# ASD2020.net
KiCad netlist of a schematic drawn in EAGLE
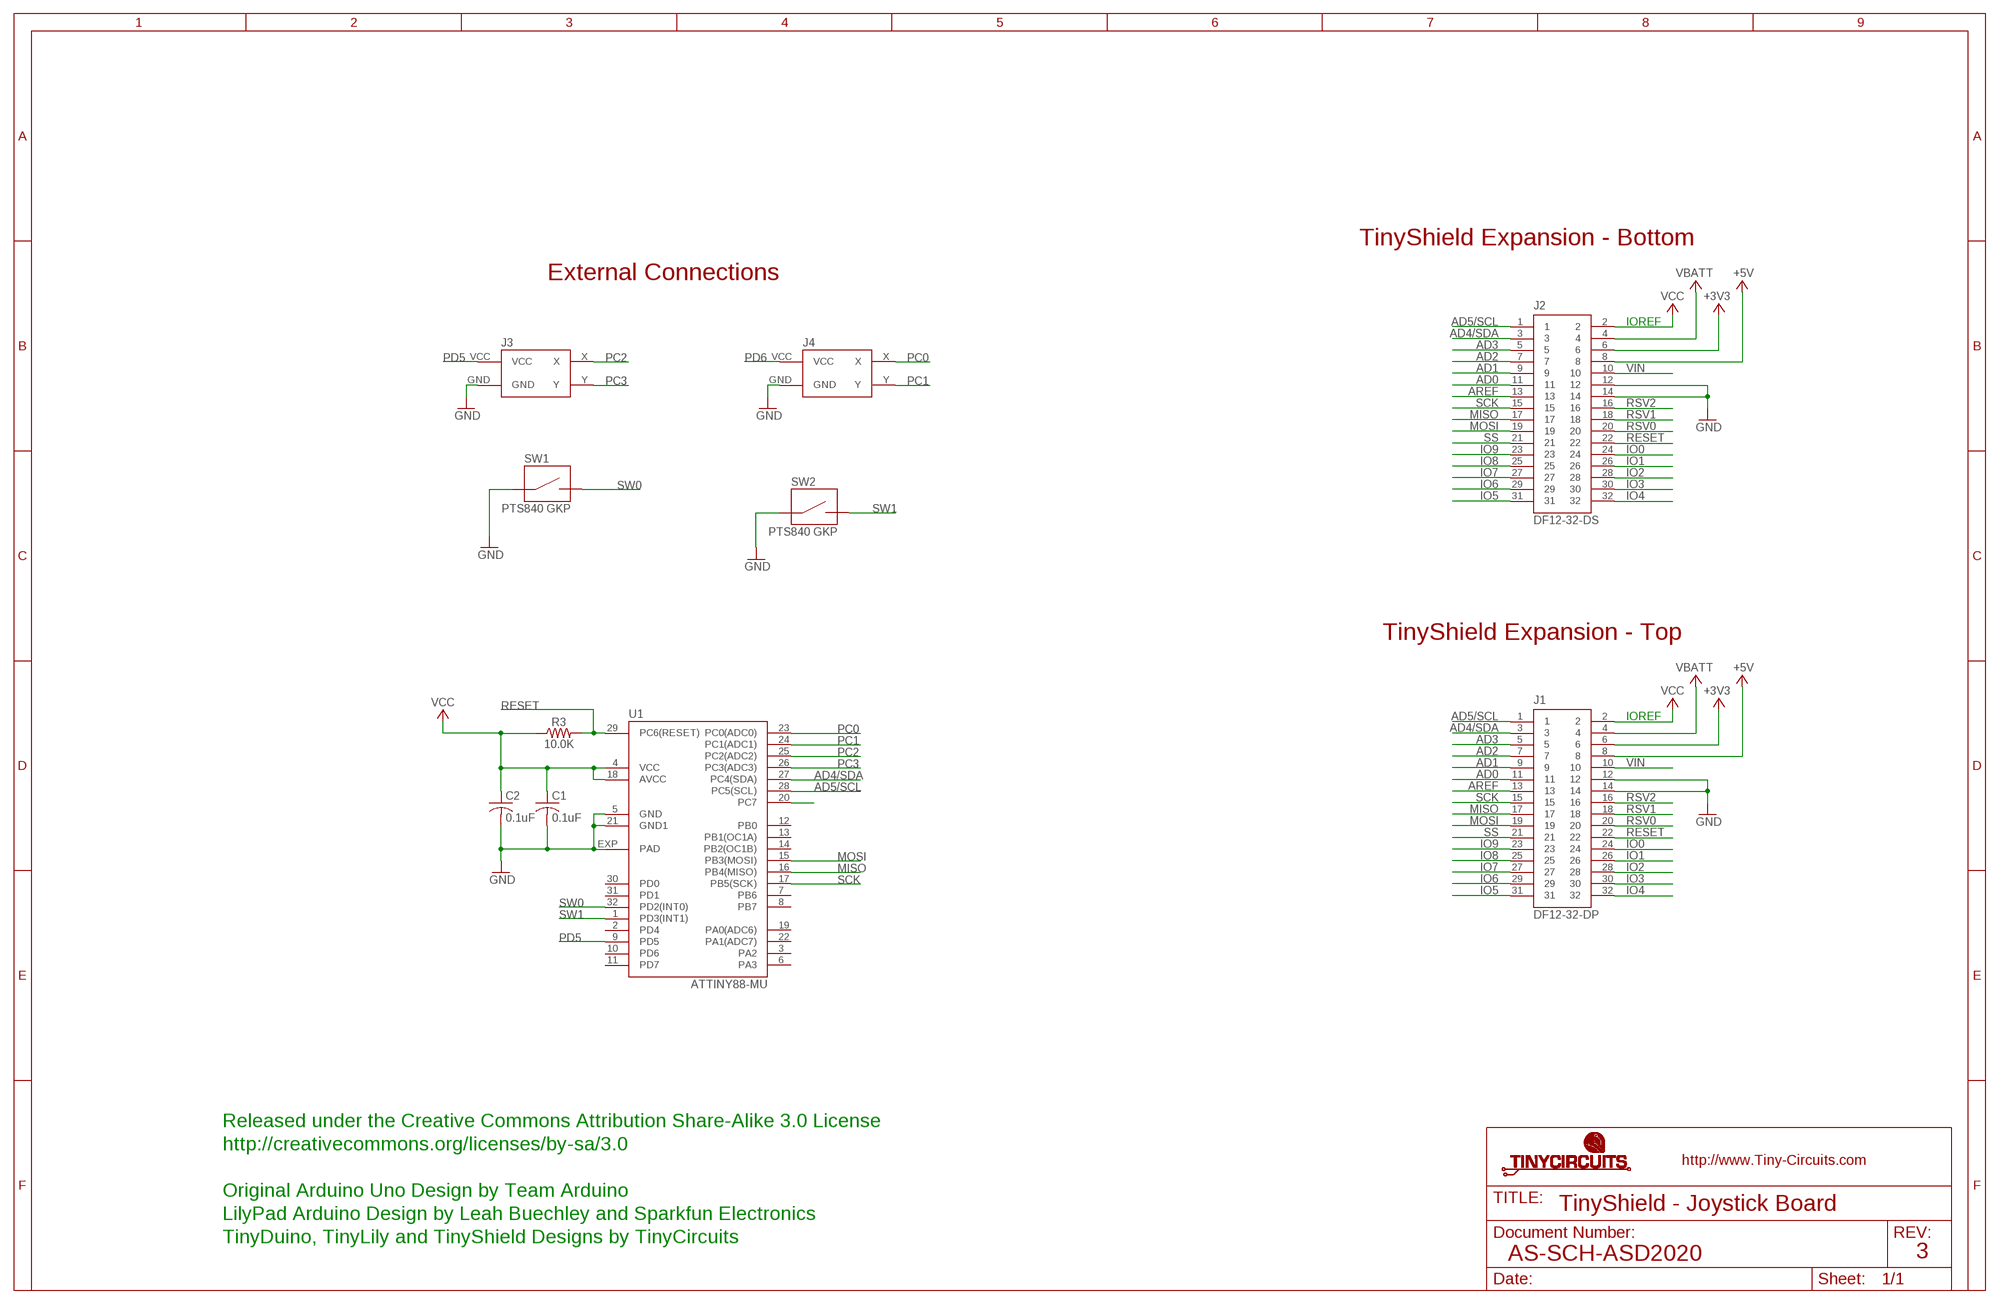
[diagram p0: schematic, sheet 1]

(export (version "E")
  (design (tool "Eeschema 10.0.6"))
  (components
    (comp (ref "C1")
      (value "0.1uF")
      (footprint "eagle-import:C0402")
      (fields (field (name "PARTNO") "AS-ITM-00008"))
      (libsource (lib "eagle-import") (part "AS-ITM-00008"))
    )
    (comp (ref "C2")
      (value "0.1uF")
      (footprint "eagle-import:C0402")
      (fields (field (name "PARTNO") "AS-ITM-00008"))
      (libsource (lib "eagle-import") (part "AS-ITM-00008"))
    )
    (comp (ref "J1")
      (value "DF12-32-DP")
      (footprint "eagle-import:DF12-32-DP")
      (fields (field (name "PARTNO") "AS-ITM-00015") (field (name "PARTNO_1") "AS-ITM-00015"))
      (libsource (lib "eagle-import") (part "AS-ITM-00015"))
    )
    (comp (ref "J2")
      (value "DF12-32-DS")
      (footprint "eagle-import:DF12-32-DS")
      (fields (field (name "PARTNO") "AS-ITM-00012") (field (name "PARTNO_1") "AS-ITM-00012"))
      (libsource (lib "eagle-import") (part "AS-ITM-00012"))
    )
    (comp (ref "J3")
      (value "AS-ITM-00235")
      (footprint "eagle-import:PSPJOYSTICK")
      (libsource (lib "eagle-import") (part "AS-ITM-00235"))
    )
    (comp (ref "J4")
      (value "AS-ITM-00235")
      (footprint "eagle-import:PSPJOYSTICK")
      (libsource (lib "eagle-import") (part "AS-ITM-00235"))
    )
    (comp (ref "R3")
      (value "10.0K")
      (footprint "eagle-import:0402")
      (fields (field (name "PARTNO") "AS-ITM-00032"))
      (libsource (lib "eagle-import") (part "AS-ITM-00032"))
    )
    (comp (ref "SW1")
      (value "PTS840 GKP")
      (footprint "eagle-import:PTS840GKP")
      (fields (field (name "PARTNO") "AS-ITM-00236"))
      (libsource (lib "eagle-import") (part "AS-ITM-00236"))
    )
    (comp (ref "SW2")
      (value "PTS840 GKP")
      (footprint "eagle-import:PTS840GKP")
      (fields (field (name "PARTNO") "AS-ITM-00236"))
      (libsource (lib "eagle-import") (part "AS-ITM-00236"))
    )
    (comp (ref "U1")
      (value "ATTINY88-MU")
      (footprint "eagle-import:ATMEL_QFN32")
      (fields (field (name "PARTNO") "AS-ITM-00214"))
      (libsource (lib "eagle-import") (part "AS-ITM-00214"))
    )
  )
  (nets
    (net (code "1") (name "+3V3") (class "Default")
      (node (ref "J1") (pin "6") (pinfunction "6_6") (pintype "bidirectional"))
      (node (ref "J2") (pin "6") (pinfunction "6_6") (pintype "bidirectional"))
    )
    (net (code "2") (name "+5V") (class "Default")
      (node (ref "J1") (pin "8") (pinfunction "8_8") (pintype "bidirectional"))
      (node (ref "J2") (pin "8") (pinfunction "8_8") (pintype "bidirectional"))
    )
    (net (code "3") (name "/AD0") (class "Default")
      (node (ref "J1") (pin "11") (pinfunction "11_11") (pintype "bidirectional"))
      (node (ref "J2") (pin "11") (pinfunction "11_11") (pintype "bidirectional"))
    )
    (net (code "4") (name "/AD1") (class "Default")
      (node (ref "J1") (pin "9") (pinfunction "9_9") (pintype "bidirectional"))
      (node (ref "J2") (pin "9") (pinfunction "9_9") (pintype "bidirectional"))
    )
    (net (code "5") (name "/AD2") (class "Default")
      (node (ref "J1") (pin "7") (pinfunction "7_7") (pintype "bidirectional"))
      (node (ref "J2") (pin "7") (pinfunction "7_7") (pintype "bidirectional"))
    )
    (net (code "6") (name "/AD3") (class "Default")
      (node (ref "J1") (pin "5") (pinfunction "5_5") (pintype "bidirectional"))
      (node (ref "J2") (pin "5") (pinfunction "5_5") (pintype "bidirectional"))
    )
    (net (code "7") (name "/AD4{slash}SDA") (class "Default")
      (node (ref "J1") (pin "3") (pinfunction "3_3") (pintype "bidirectional"))
      (node (ref "J2") (pin "3") (pinfunction "3_3") (pintype "bidirectional"))
      (node (ref "U1") (pin "27") (pinfunction "PC4(SDA)_27") (pintype "bidirectional"))
    )
    (net (code "8") (name "/AD5{slash}SCL") (class "Default")
      (node (ref "J1") (pin "1") (pinfunction "1_1") (pintype "bidirectional"))
      (node (ref "J2") (pin "1") (pinfunction "1_1") (pintype "bidirectional"))
      (node (ref "U1") (pin "28") (pinfunction "PC5(SCL)_28") (pintype "bidirectional"))
    )
    (net (code "9") (name "/AREF") (class "Default")
      (node (ref "J1") (pin "13") (pinfunction "13_13") (pintype "bidirectional"))
      (node (ref "J2") (pin "13") (pinfunction "13_13") (pintype "bidirectional"))
    )
    (net (code "10") (name "/IO0") (class "Default")
      (node (ref "J1") (pin "24") (pinfunction "24_24") (pintype "bidirectional"))
      (node (ref "J2") (pin "24") (pinfunction "24_24") (pintype "bidirectional"))
    )
    (net (code "11") (name "/IO1") (class "Default")
      (node (ref "J1") (pin "26") (pinfunction "26_26") (pintype "bidirectional"))
      (node (ref "J2") (pin "26") (pinfunction "26_26") (pintype "bidirectional"))
    )
    (net (code "12") (name "/IO2") (class "Default")
      (node (ref "J1") (pin "28") (pinfunction "28_28") (pintype "bidirectional"))
      (node (ref "J2") (pin "28") (pinfunction "28_28") (pintype "bidirectional"))
    )
    (net (code "13") (name "/IO3") (class "Default")
      (node (ref "J1") (pin "30") (pinfunction "30_30") (pintype "bidirectional"))
      (node (ref "J2") (pin "30") (pinfunction "30_30") (pintype "bidirectional"))
    )
    (net (code "14") (name "/IO4") (class "Default")
      (node (ref "J1") (pin "32") (pinfunction "32_32") (pintype "bidirectional"))
      (node (ref "J2") (pin "32") (pinfunction "32_32") (pintype "bidirectional"))
    )
    (net (code "15") (name "/IO5") (class "Default")
      (node (ref "J1") (pin "31") (pinfunction "31_31") (pintype "bidirectional"))
      (node (ref "J2") (pin "31") (pinfunction "31_31") (pintype "bidirectional"))
    )
    (net (code "16") (name "/IO6") (class "Default")
      (node (ref "J1") (pin "29") (pinfunction "29_29") (pintype "bidirectional"))
      (node (ref "J2") (pin "29") (pinfunction "29_29") (pintype "bidirectional"))
    )
    (net (code "17") (name "/IO7") (class "Default")
      (node (ref "J1") (pin "27") (pinfunction "27_27") (pintype "bidirectional"))
      (node (ref "J2") (pin "27") (pinfunction "27_27") (pintype "bidirectional"))
    )
    (net (code "18") (name "/IO8") (class "Default")
      (node (ref "J1") (pin "25") (pinfunction "25_25") (pintype "bidirectional"))
      (node (ref "J2") (pin "25") (pinfunction "25_25") (pintype "bidirectional"))
    )
    (net (code "19") (name "/IO9") (class "Default")
      (node (ref "J1") (pin "23") (pinfunction "23_23") (pintype "bidirectional"))
      (node (ref "J2") (pin "23") (pinfunction "23_23") (pintype "bidirectional"))
    )
    (net (code "20") (name "/MISO") (class "Default")
      (node (ref "J1") (pin "17") (pinfunction "17_17") (pintype "bidirectional"))
      (node (ref "J2") (pin "17") (pinfunction "17_17") (pintype "bidirectional"))
      (node (ref "U1") (pin "16") (pinfunction "PB4(MISO)_16") (pintype "bidirectional"))
    )
    (net (code "21") (name "/MOSI") (class "Default")
      (node (ref "J1") (pin "19") (pinfunction "19_19") (pintype "bidirectional"))
      (node (ref "J2") (pin "19") (pinfunction "19_19") (pintype "bidirectional"))
      (node (ref "U1") (pin "15") (pinfunction "PB3(MOSI)_15") (pintype "bidirectional"))
    )
    (net (code "22") (name "/PC0") (class "Default")
      (node (ref "J4") (pin "X") (pinfunction "X_X") (pintype "bidirectional"))
      (node (ref "U1") (pin "23") (pinfunction "PC0(ADC0)_23") (pintype "bidirectional"))
    )
    (net (code "23") (name "/PC1") (class "Default")
      (node (ref "J4") (pin "Y") (pinfunction "Y_Y") (pintype "bidirectional"))
      (node (ref "U1") (pin "24") (pinfunction "PC1(ADC1)_24") (pintype "bidirectional"))
    )
    (net (code "24") (name "/PC2") (class "Default")
      (node (ref "J3") (pin "X") (pinfunction "X_X") (pintype "bidirectional"))
      (node (ref "U1") (pin "25") (pinfunction "PC2(ADC2)_25") (pintype "bidirectional"))
    )
    (net (code "25") (name "/PC3") (class "Default")
      (node (ref "J3") (pin "Y") (pinfunction "Y_Y") (pintype "bidirectional"))
      (node (ref "U1") (pin "26") (pinfunction "PC3(ADC3)_26") (pintype "bidirectional"))
    )
    (net (code "26") (name "/PD5") (class "Default")
      (node (ref "J3") (pin "VCC") (pinfunction "VCC_VCC") (pintype "bidirectional"))
      (node (ref "U1") (pin "9") (pinfunction "PD5_9") (pintype "bidirectional"))
    )
    (net (code "27") (name "/PD6") (class "Default")
      (node (ref "J4") (pin "VCC") (pinfunction "VCC_VCC") (pintype "bidirectional"))
      (node (ref "U1") (pin "20") (pinfunction "PC7_20") (pintype "bidirectional"))
    )
    (net (code "28") (name "/RESET") (class "Default")
      (node (ref "J1") (pin "22") (pinfunction "22_22") (pintype "bidirectional"))
      (node (ref "J2") (pin "22") (pinfunction "22_22") (pintype "bidirectional"))
      (node (ref "R3") (pin "2") (pinfunction "2_2") (pintype "passive"))
      (node (ref "U1") (pin "29") (pinfunction "PC6(RESET)_29") (pintype "bidirectional"))
    )
    (net (code "29") (name "/RSV0") (class "Default")
      (node (ref "J1") (pin "20") (pinfunction "20_20") (pintype "bidirectional"))
      (node (ref "J2") (pin "20") (pinfunction "20_20") (pintype "bidirectional"))
    )
    (net (code "30") (name "/RSV1") (class "Default")
      (node (ref "J1") (pin "18") (pinfunction "18_18") (pintype "bidirectional"))
      (node (ref "J2") (pin "18") (pinfunction "18_18") (pintype "bidirectional"))
    )
    (net (code "31") (name "/RSV2") (class "Default")
      (node (ref "J1") (pin "16") (pinfunction "16_16") (pintype "bidirectional"))
      (node (ref "J2") (pin "16") (pinfunction "16_16") (pintype "bidirectional"))
    )
    (net (code "32") (name "/SCK") (class "Default")
      (node (ref "J1") (pin "15") (pinfunction "15_15") (pintype "bidirectional"))
      (node (ref "J2") (pin "15") (pinfunction "15_15") (pintype "bidirectional"))
      (node (ref "U1") (pin "17") (pinfunction "PB5(SCK)_17") (pintype "bidirectional"))
    )
    (net (code "33") (name "/SS") (class "Default")
      (node (ref "J1") (pin "21") (pinfunction "21_21") (pintype "bidirectional"))
      (node (ref "J2") (pin "21") (pinfunction "21_21") (pintype "bidirectional"))
    )
    (net (code "34") (name "/SW0") (class "Default")
      (node (ref "SW1") (pin "3") (pinfunction "2_3") (pintype "bidirectional"))
      (node (ref "SW1") (pin "4") (pinfunction "2_4") (pintype "bidirectional"))
      (node (ref "U1") (pin "32") (pinfunction "PD2(INT0)_32") (pintype "bidirectional"))
    )
    (net (code "35") (name "/SW1") (class "Default")
      (node (ref "SW2") (pin "3") (pinfunction "2_3") (pintype "bidirectional"))
      (node (ref "SW2") (pin "4") (pinfunction "2_4") (pintype "bidirectional"))
      (node (ref "U1") (pin "1") (pinfunction "PD3(INT1)_1") (pintype "bidirectional"))
    )
    (net (code "36") (name "/VIN") (class "Default")
      (node (ref "J1") (pin "10") (pinfunction "10_10") (pintype "bidirectional"))
      (node (ref "J2") (pin "10") (pinfunction "10_10") (pintype "bidirectional"))
    )
    (net (code "37") (name "GND") (class "Default")
      (node (ref "C1") (pin "2") (pinfunction "2_2") (pintype "passive"))
      (node (ref "C2") (pin "2") (pinfunction "2_2") (pintype "passive"))
      (node (ref "J1") (pin "12") (pinfunction "12_12") (pintype "bidirectional"))
      (node (ref "J1") (pin "14") (pinfunction "14_14") (pintype "bidirectional"))
      (node (ref "J2") (pin "12") (pinfunction "12_12") (pintype "bidirectional"))
      (node (ref "J2") (pin "14") (pinfunction "14_14") (pintype "bidirectional"))
      (node (ref "J3") (pin "GND") (pinfunction "GND_GND") (pintype "bidirectional"))
      (node (ref "J4") (pin "GND") (pinfunction "GND_GND") (pintype "bidirectional"))
      (node (ref "SW1") (pin "1") (pinfunction "1_1") (pintype "bidirectional"))
      (node (ref "SW1") (pin "2") (pinfunction "1_2") (pintype "bidirectional"))
      (node (ref "SW2") (pin "1") (pinfunction "1_1") (pintype "bidirectional"))
      (node (ref "SW2") (pin "2") (pinfunction "1_2") (pintype "bidirectional"))
      (node (ref "U1") (pin "21") (pinfunction "GND1_21") (pintype "bidirectional"))
      (node (ref "U1") (pin "5") (pinfunction "GND_5") (pintype "bidirectional"))
      (node (ref "U1") (pin "EXP") (pinfunction "PAD_EXP") (pintype "bidirectional"))
    )
    (net (code "38") (name "VBATT") (class "Default")
      (node (ref "J1") (pin "4") (pinfunction "4_4") (pintype "bidirectional"))
      (node (ref "J2") (pin "4") (pinfunction "4_4") (pintype "bidirectional"))
    )
    (net (code "39") (name "VCC") (class "Default")
      (node (ref "C1") (pin "1") (pinfunction "1_1") (pintype "passive"))
      (node (ref "C2") (pin "1") (pinfunction "1_1") (pintype "passive"))
      (node (ref "J1") (pin "2") (pinfunction "2_2") (pintype "bidirectional"))
      (node (ref "J2") (pin "2") (pinfunction "2_2") (pintype "bidirectional"))
      (node (ref "R3") (pin "1") (pinfunction "1_1") (pintype "passive"))
      (node (ref "U1") (pin "18") (pinfunction "AVCC_18") (pintype "bidirectional"))
      (node (ref "U1") (pin "4") (pinfunction "VCC_4") (pintype "bidirectional"))
    )
    (net (code "40") (name "unconnected-(U1-PA0(ADC6)-Pad19)") (class "Default")
      (node (ref "U1") (pin "19") (pinfunction "PA0(ADC6)_19") (pintype "bidirectional"))
    )
    (net (code "41") (name "unconnected-(U1-PA1(ADC7)-Pad22)") (class "Default")
      (node (ref "U1") (pin "22") (pinfunction "PA1(ADC7)_22") (pintype "bidirectional"))
    )
    (net (code "42") (name "unconnected-(U1-PA2-Pad3)") (class "Default")
      (node (ref "U1") (pin "3") (pinfunction "PA2_3") (pintype "bidirectional"))
    )
    (net (code "43") (name "unconnected-(U1-PA3-Pad6)") (class "Default")
      (node (ref "U1") (pin "6") (pinfunction "PA3_6") (pintype "bidirectional"))
    )
    (net (code "44") (name "unconnected-(U1-PB0-Pad12)") (class "Default")
      (node (ref "U1") (pin "12") (pinfunction "PB0_12") (pintype "bidirectional"))
    )
    (net (code "45") (name "unconnected-(U1-PB1(OC1A)-Pad13)") (class "Default")
      (node (ref "U1") (pin "13") (pinfunction "PB1(OC1A)_13") (pintype "bidirectional"))
    )
    (net (code "46") (name "unconnected-(U1-PB2(OC1B)-Pad14)") (class "Default")
      (node (ref "U1") (pin "14") (pinfunction "PB2(OC1B)_14") (pintype "bidirectional"))
    )
    (net (code "47") (name "unconnected-(U1-PB6-Pad7)") (class "Default")
      (node (ref "U1") (pin "7") (pinfunction "PB6_7") (pintype "bidirectional"))
    )
    (net (code "48") (name "unconnected-(U1-PB7-Pad8)") (class "Default")
      (node (ref "U1") (pin "8") (pinfunction "PB7_8") (pintype "bidirectional"))
    )
    (net (code "49") (name "unconnected-(U1-PD0-Pad30)") (class "Default")
      (node (ref "U1") (pin "30") (pinfunction "PD0_30") (pintype "bidirectional"))
    )
    (net (code "50") (name "unconnected-(U1-PD1-Pad31)") (class "Default")
      (node (ref "U1") (pin "31") (pinfunction "PD1_31") (pintype "bidirectional"))
    )
    (net (code "51") (name "unconnected-(U1-PD4-Pad2)") (class "Default")
      (node (ref "U1") (pin "2") (pinfunction "PD4_2") (pintype "bidirectional"))
    )
    (net (code "52") (name "unconnected-(U1-PD6-Pad10)") (class "Default")
      (node (ref "U1") (pin "10") (pinfunction "PD6_10") (pintype "bidirectional"))
    )
    (net (code "53") (name "unconnected-(U1-PD7-Pad11)") (class "Default")
      (node (ref "U1") (pin "11") (pinfunction "PD7_11") (pintype "bidirectional"))
    )
  )
)
